# ha-pc-switch-revB.net
KiCad netlist of a schematic drawn in EAGLE
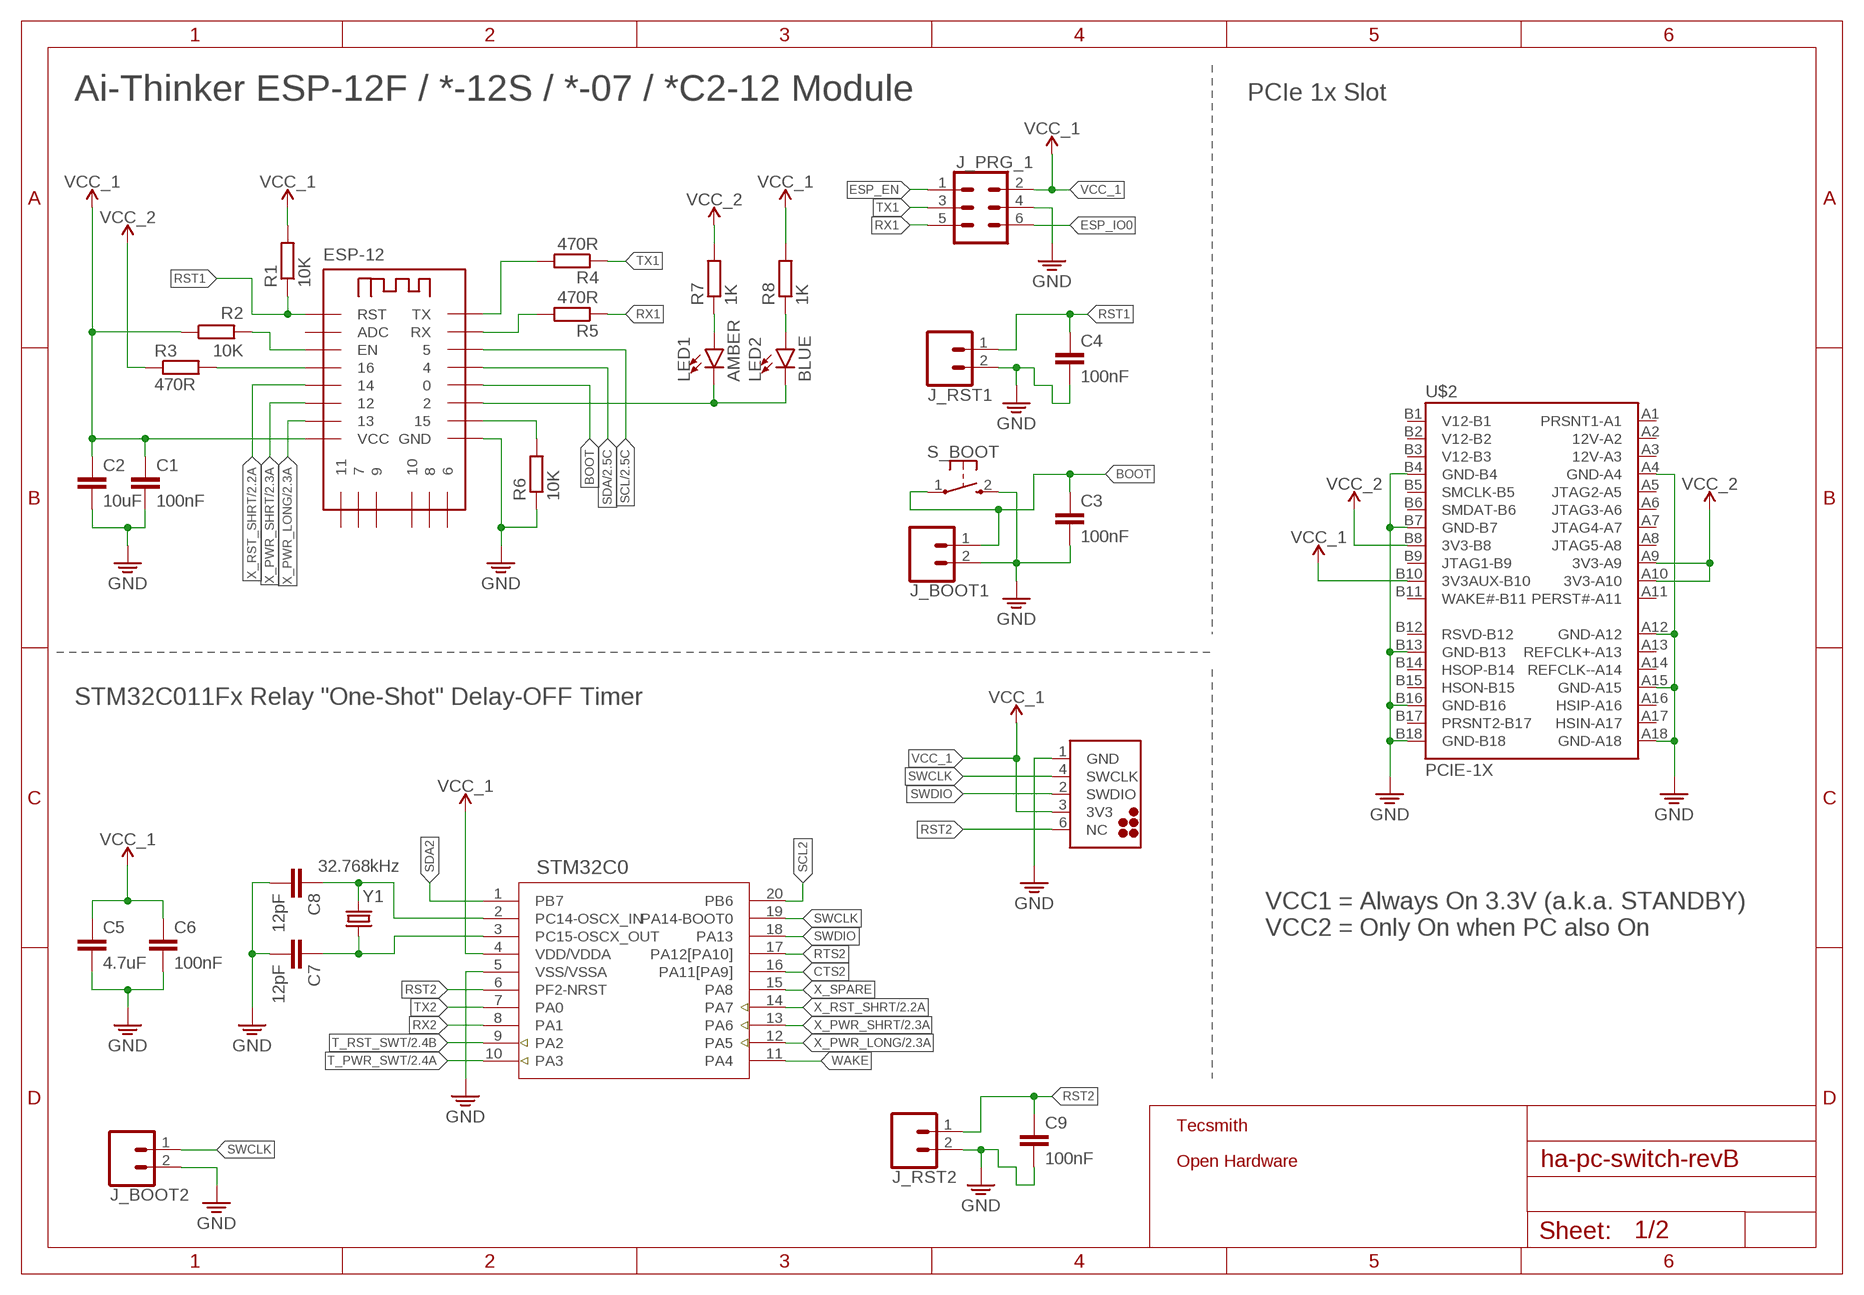
[diagram p0: schematic, sheet 1]
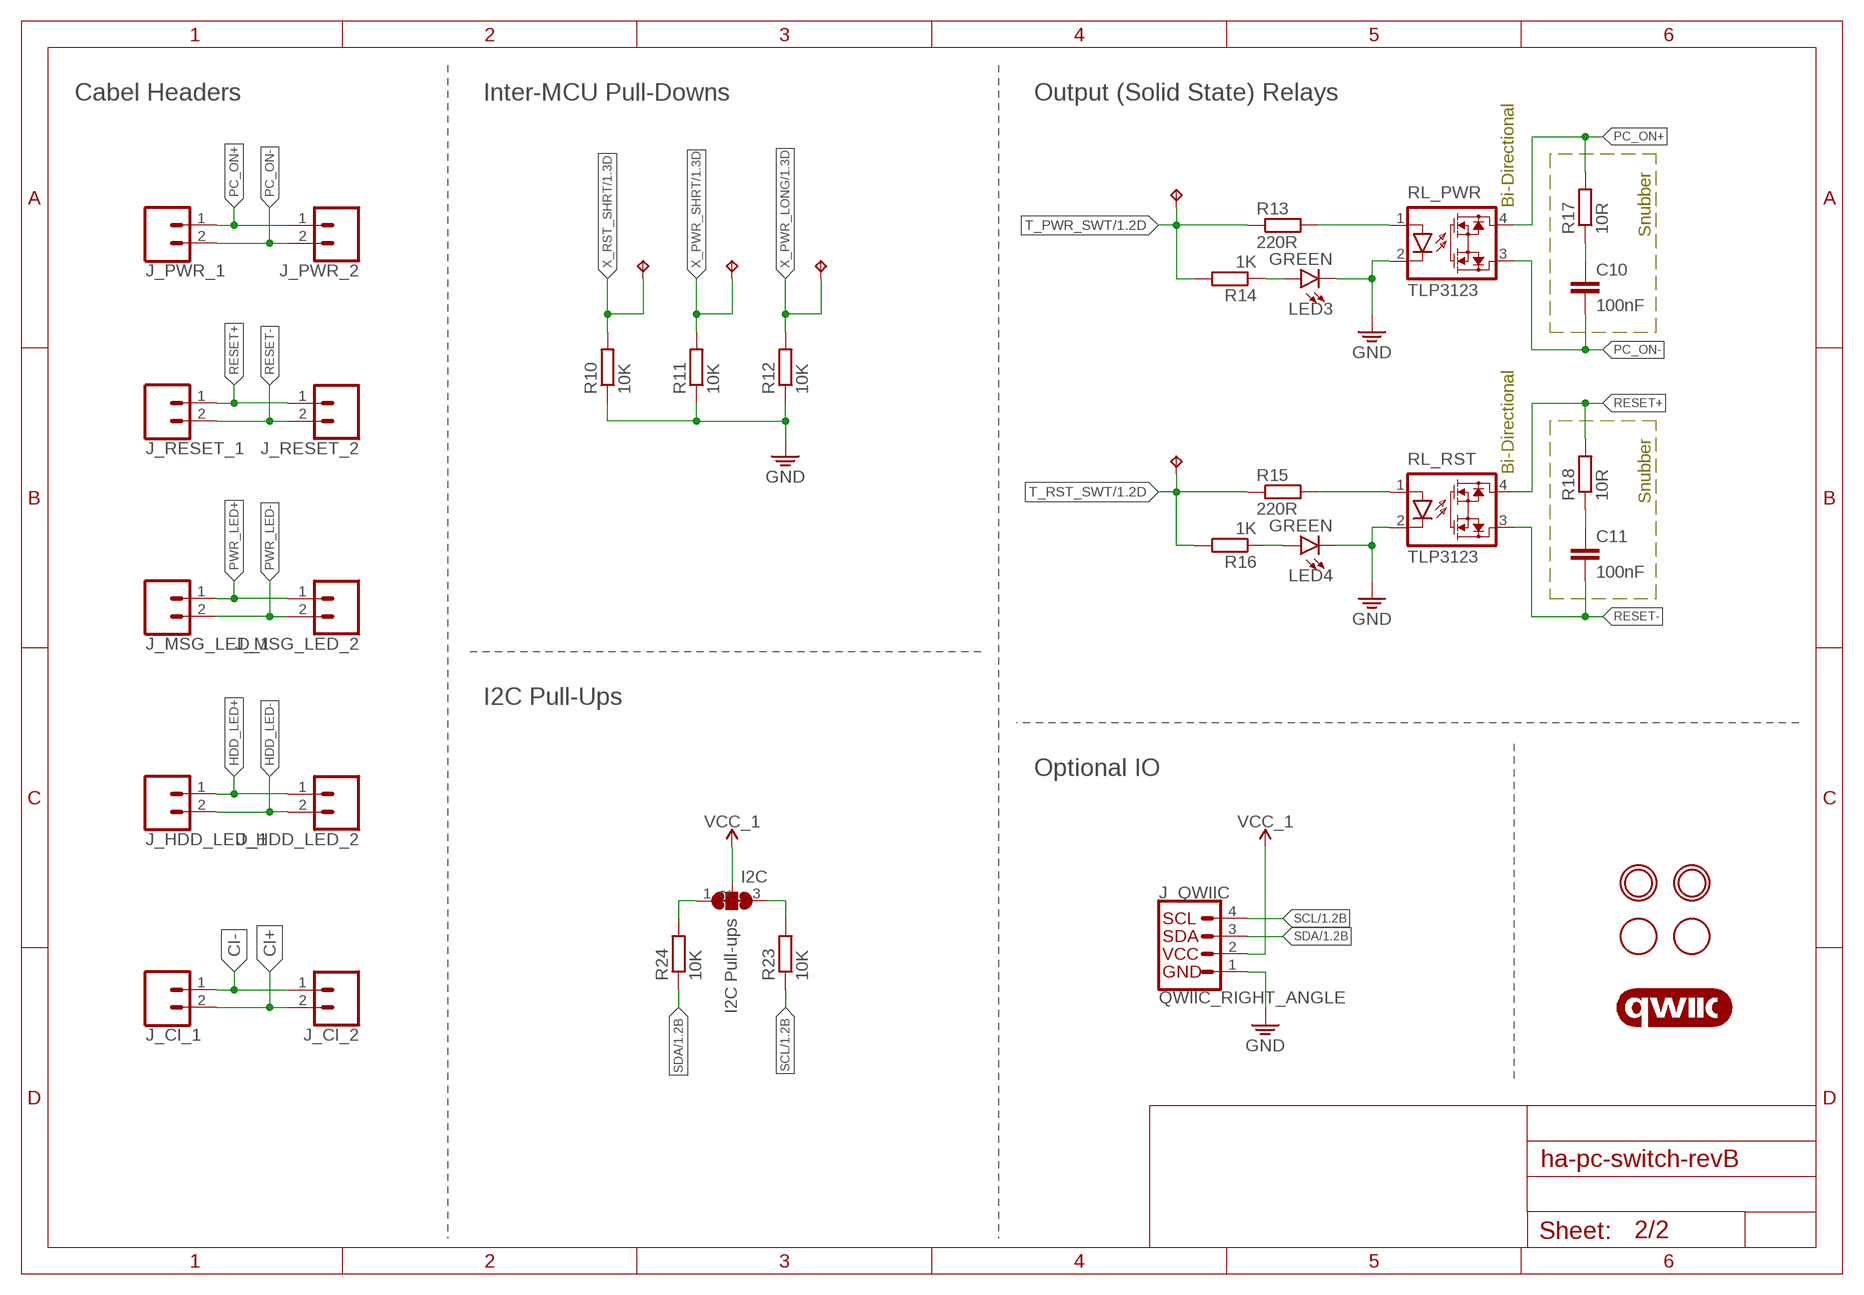
[diagram p1: schematic, sheet 2]

(export (version "E")
  (design (tool "Eeschema 10.0.6"))
  (components
    (comp (ref "C10")
      (value "100nF")
      (footprint "eagle-import:C0603")
      (libsource (lib "eagle-import") (part "C-EUC0603"))
    )
    (comp (ref "C11")
      (value "100nF")
      (footprint "eagle-import:C0603")
      (libsource (lib "eagle-import") (part "C-EUC0603"))
    )
    (comp (ref "I2C")
      (value "JUMPER-1X3-CLOSED-2")
      (footprint "eagle-import:SOLDERJUMPER_CLOSEDWIRE-3-2")
      (libsource (lib "eagle-import") (part "JUMPER-1X3-CLOSED-2"))
    )
    (comp (ref "J_CI_1")
      (value "CONN_021X02_NO_SILK")
      (footprint "eagle-import:1X02_NO_SILK")
      (libsource (lib "eagle-import") (part "CONN_021X02_NO_SILK"))
    )
    (comp (ref "J_CI_2")
      (value "CONN_021X02_NO_SILK")
      (footprint "eagle-import:1X02_NO_SILK")
      (libsource (lib "eagle-import") (part "CONN_021X02_NO_SILK"))
    )
    (comp (ref "J_HDD_LED_1")
      (value "CONN_021X02_NO_SILK")
      (footprint "eagle-import:1X02_NO_SILK")
      (libsource (lib "eagle-import") (part "CONN_021X02_NO_SILK"))
    )
    (comp (ref "J_HDD_LED_2")
      (value "CONN_021X02_NO_SILK")
      (footprint "eagle-import:1X02_NO_SILK")
      (libsource (lib "eagle-import") (part "CONN_021X02_NO_SILK"))
    )
    (comp (ref "J_MSG_LED_1")
      (value "CONN_021X02_NO_SILK")
      (footprint "eagle-import:1X02_NO_SILK")
      (libsource (lib "eagle-import") (part "CONN_021X02_NO_SILK"))
    )
    (comp (ref "J_MSG_LED_2")
      (value "CONN_021X02_NO_SILK")
      (footprint "eagle-import:1X02_NO_SILK")
      (libsource (lib "eagle-import") (part "CONN_021X02_NO_SILK"))
    )
    (comp (ref "J_PWR_1")
      (value "CONN_021X02_NO_SILK")
      (footprint "eagle-import:1X02_NO_SILK")
      (libsource (lib "eagle-import") (part "CONN_021X02_NO_SILK"))
    )
    (comp (ref "J_PWR_2")
      (value "CONN_021X02_NO_SILK")
      (footprint "eagle-import:1X02_NO_SILK")
      (libsource (lib "eagle-import") (part "CONN_021X02_NO_SILK"))
    )
    (comp (ref "J_QWIIC")
      (value "QWIIC_RIGHT_ANGLE")
      (footprint "eagle-import:JST04_1MM_RA")
      (libsource (lib "eagle-import") (part "QWIIC_CONNECTORJS-1MM"))
    )
    (comp (ref "J_RESET_1")
      (value "CONN_021X02_NO_SILK")
      (footprint "eagle-import:1X02_NO_SILK")
      (libsource (lib "eagle-import") (part "CONN_021X02_NO_SILK"))
    )
    (comp (ref "J_RESET_2")
      (value "CONN_021X02_NO_SILK")
      (footprint "eagle-import:1X02_NO_SILK")
      (libsource (lib "eagle-import") (part "CONN_021X02_NO_SILK"))
    )
    (comp (ref "LED3")
      (value "GREEN")
      (footprint "eagle-import:LED-0603")
      (libsource (lib "eagle-import") (part "LED-GREEN0603"))
    )
    (comp (ref "LED4")
      (value "GREEN")
      (footprint "eagle-import:LED-0603")
      (libsource (lib "eagle-import") (part "LED-GREEN0603"))
    )
    (comp (ref "LOGO2")
      (value "QWIIC_LOGO_4MM")
      (footprint "eagle-import:QWIIC_4MM")
      (libsource (lib "eagle-import") (part "QWIIC_LOGO_4MM"))
    )
    (comp (ref "R10")
      (value "10K")
      (footprint "eagle-import:R0603")
      (libsource (lib "eagle-import") (part "R-EU_R0603"))
    )
    (comp (ref "R11")
      (value "10K")
      (footprint "eagle-import:R0603")
      (libsource (lib "eagle-import") (part "R-EU_R0603"))
    )
    (comp (ref "R12")
      (value "10K")
      (footprint "eagle-import:R0603")
      (libsource (lib "eagle-import") (part "R-EU_R0603"))
    )
    (comp (ref "R13")
      (value "220R")
      (footprint "eagle-import:R0603")
      (libsource (lib "eagle-import") (part "R-EU_R0603"))
    )
    (comp (ref "R14")
      (value "1K")
      (footprint "eagle-import:R0603")
      (libsource (lib "eagle-import") (part "R-EU_R0603"))
    )
    (comp (ref "R15")
      (value "220R")
      (footprint "eagle-import:R0603")
      (libsource (lib "eagle-import") (part "R-EU_R0603"))
    )
    (comp (ref "R16")
      (value "1K")
      (footprint "eagle-import:R0603")
      (libsource (lib "eagle-import") (part "R-EU_R0603"))
    )
    (comp (ref "R17")
      (value "10R")
      (footprint "eagle-import:R0603")
      (libsource (lib "eagle-import") (part "R-EU_R0603"))
    )
    (comp (ref "R18")
      (value "10R")
      (footprint "eagle-import:R0603")
      (libsource (lib "eagle-import") (part "R-EU_R0603"))
    )
    (comp (ref "R23")
      (value "10K")
      (footprint "eagle-import:R0603")
      (libsource (lib "eagle-import") (part "R-EU_R0603"))
    )
    (comp (ref "R24")
      (value "10K")
      (footprint "eagle-import:R0603")
      (libsource (lib "eagle-import") (part "R-EU_R0603"))
    )
    (comp (ref "RL_PWR")
      (value "TLP3123")
      (footprint "eagle-import:SOP4_TOS")
      (libsource (lib "eagle-import") (part "TLP3123"))
    )
    (comp (ref "RL_RST")
      (value "TLP3123")
      (footprint "eagle-import:SOP4_TOS")
      (libsource (lib "eagle-import") (part "TLP3123"))
    )
    (comp (ref "TP6")
      (value "TPTP16SQ")
      (footprint "eagle-import:TP16SQ")
      (libsource (lib "eagle-import") (part "TPTP16SQ"))
    )
    (comp (ref "TP7")
      (value "TPTP16SQ")
      (footprint "eagle-import:TP16SQ")
      (libsource (lib "eagle-import") (part "TPTP16SQ"))
    )
    (comp (ref "TP8")
      (value "TPTP16SQ")
      (footprint "eagle-import:TP16SQ")
      (libsource (lib "eagle-import") (part "TPTP16SQ"))
    )
    (comp (ref "TP9")
      (value "TPTP16SQ")
      (footprint "eagle-import:TP16SQ")
      (libsource (lib "eagle-import") (part "TPTP16SQ"))
    )
    (comp (ref "TP10")
      (value "TPTP16SQ")
      (footprint "eagle-import:TP16SQ")
      (libsource (lib "eagle-import") (part "TPTP16SQ"))
    )
    (comp (ref "U$9")
      (value "MOUNTINGHOLE3.0THIN")
      (footprint "eagle-import:MOUNTINGHOLE_3.0_PLATEDTHIN")
      (libsource (lib "eagle-import") (part "MOUNTINGHOLE3.0THIN"))
    )
    (comp (ref "U$11")
      (value "MOUNTINGHOLE3.0THIN")
      (footprint "eagle-import:MOUNTINGHOLE_3.0_PLATEDTHIN")
      (libsource (lib "eagle-import") (part "MOUNTINGHOLE3.0THIN"))
    )
    (comp (ref "U$15")
      (value "FIDUCIAL")
      (footprint "eagle-import:FIDUCIAL_1MM")
      (libsource (lib "eagle-import") (part "FIDUCIAL"))
    )
    (comp (ref "U$16")
      (value "FIDUCIAL")
      (footprint "eagle-import:FIDUCIAL_1MM")
      (libsource (lib "eagle-import") (part "FIDUCIAL"))
    )
    (comp (ref "C1")
      (value "100nF")
      (footprint "eagle-import:C0603")
      (libsource (lib "eagle-import") (part "C-EUC0603"))
    )
    (comp (ref "C2")
      (value "10uF")
      (footprint "eagle-import:C0603")
      (libsource (lib "eagle-import") (part "C-EUC0603"))
    )
    (comp (ref "C3")
      (value "100nF")
      (footprint "eagle-import:C0603")
      (libsource (lib "eagle-import") (part "C-EUC0603"))
    )
    (comp (ref "C4")
      (value "100nF")
      (footprint "eagle-import:C0603")
      (libsource (lib "eagle-import") (part "C-EUC0603"))
    )
    (comp (ref "C5")
      (value "4.7uF")
      (footprint "eagle-import:C0603")
      (libsource (lib "eagle-import") (part "C-EUC0603"))
    )
    (comp (ref "C6")
      (value "100nF")
      (footprint "eagle-import:C0603")
      (libsource (lib "eagle-import") (part "C-EUC0603"))
    )
    (comp (ref "C7")
      (value "12pF")
      (footprint "eagle-import:C0603")
      (libsource (lib "eagle-import") (part "C-EUC0603"))
    )
    (comp (ref "C8")
      (value "12pF")
      (footprint "eagle-import:C0603")
      (libsource (lib "eagle-import") (part "C-EUC0603"))
    )
    (comp (ref "C9")
      (value "100nF")
      (footprint "eagle-import:C0603")
      (libsource (lib "eagle-import") (part "C-EUC0603"))
    )
    (comp (ref "ESP-12")
      (value "ESPRESSIF-ESP-12F&ESMD")
      (footprint "eagle-import:ESP8266-ESP-12E")
      (libsource (lib "eagle-import") (part "ESPRESSIF-ESP-12F&ESMD"))
    )
    (comp (ref "J_BOOT1")
      (value "CONN_021X02_NO_SILK")
      (footprint "eagle-import:1X02_NO_SILK")
      (libsource (lib "eagle-import") (part "CONN_021X02_NO_SILK"))
    )
    (comp (ref "J_BOOT2")
      (value "CONN_021X02_NO_SILK")
      (footprint "eagle-import:1X02_NO_SILK")
      (libsource (lib "eagle-import") (part "CONN_021X02_NO_SILK"))
    )
    (comp (ref "J_PRG2")
      (value "NUCLEO_HEADER")
      (footprint "eagle-import:NUCLEO")
      (libsource (lib "eagle-import") (part "NUCLEO_HEADER"))
    )
    (comp (ref "J_PRG_1")
      (value "CONN_03X2NO_SILK")
      (footprint "eagle-import:2X3-NS")
      (libsource (lib "eagle-import") (part "CONN_03X2NO_SILK"))
    )
    (comp (ref "J_RST1")
      (value "CONN_021X02_NO_SILK")
      (footprint "eagle-import:1X02_NO_SILK")
      (libsource (lib "eagle-import") (part "CONN_021X02_NO_SILK"))
    )
    (comp (ref "J_RST2")
      (value "CONN_021X02_NO_SILK")
      (footprint "eagle-import:1X02_NO_SILK")
      (libsource (lib "eagle-import") (part "CONN_021X02_NO_SILK"))
    )
    (comp (ref "LED1")
      (value "AMBER")
      (footprint "eagle-import:LED-0603")
      (libsource (lib "eagle-import") (part "LED-GREEN0603"))
    )
    (comp (ref "LED2")
      (value "BLUE")
      (footprint "eagle-import:LED-0603")
      (libsource (lib "eagle-import") (part "LED-GREEN0603"))
    )
    (comp (ref "LOGO1")
      (value "OSHW-LOGOM")
      (footprint "eagle-import:OSHW-LOGO-M")
      (libsource (lib "eagle-import") (part "OSHW-LOGOM"))
    )
    (comp (ref "R1")
      (value "10K")
      (footprint "eagle-import:R0603")
      (libsource (lib "eagle-import") (part "R-EU_R0603"))
    )
    (comp (ref "R2")
      (value "10K")
      (footprint "eagle-import:R0603")
      (libsource (lib "eagle-import") (part "R-EU_R0603"))
    )
    (comp (ref "R3")
      (value "470R")
      (footprint "eagle-import:R0603")
      (libsource (lib "eagle-import") (part "R-EU_R0603"))
    )
    (comp (ref "R4")
      (value "470R")
      (footprint "eagle-import:R0603")
      (libsource (lib "eagle-import") (part "R-EU_R0603"))
    )
    (comp (ref "R5")
      (value "470R")
      (footprint "eagle-import:R0603")
      (libsource (lib "eagle-import") (part "R-EU_R0603"))
    )
    (comp (ref "R6")
      (value "10K")
      (footprint "eagle-import:R0603")
      (libsource (lib "eagle-import") (part "R-EU_R0603"))
    )
    (comp (ref "R7")
      (value "1K")
      (footprint "eagle-import:R0603")
      (libsource (lib "eagle-import") (part "R-EU_R0603"))
    )
    (comp (ref "R8")
      (value "1K")
      (footprint "eagle-import:R0603")
      (libsource (lib "eagle-import") (part "R-EU_R0603"))
    )
    (comp (ref "STM32C0")
      (value "STM32C011FTSSOP20_STM-M")
      (footprint "eagle-import:TSSOP20-M")
      (fields
        (field (name "MANUFACTURER_PART_NUMBER") "STM32C011F4P6")
        (field (name "COPYRIGHT") "Copyright (C) 2024 Ultra Librarian. All rights reserved.")
      )
      (libsource (lib "eagle-import") (part "STM32C011FTSSOP20_STM-M"))
    )
    (comp (ref "S_BOOT")
      (value "MOMENTARY-SWITCH-SPST-1")
      (footprint "eagle-import:SKRKAEE020")
      (libsource (lib "eagle-import") (part "MOMENTARY-SWITCH-SPST-1"))
    )
    (comp (ref "U$1")
      (value "TECSMITH-LOGOLONG")
      (footprint "eagle-import:TECSMITH-NAME")
      (libsource (lib "eagle-import") (part "TECSMITH-LOGOLONG"))
    )
    (comp (ref "U$2")
      (value "PCIE-1X")
      (footprint "eagle-import:PCIE-1X")
      (libsource (lib "eagle-import") (part "PCIE-1X"))
    )
    (comp (ref "Y1")
      (value "32.768kHz")
      (footprint "eagle-import:CRYSTAL-SMD-3.2X1.5MM")
      (libsource (lib "eagle-import") (part "CRYSTAL-32.768KHZSMD-3.2X1.5"))
    )
  )
  (nets
    (net (code "1") (name "BOOT") (class "Default")
      (node (ref "C3") (pin "1") (pinfunction "1_1") (pintype "passive"))
      (node (ref "ESP-12") (pin "GPIO0") (pinfunction "0_GPIO0") (pintype "bidirectional"))
      (node (ref "J_BOOT1") (pin "1") (pinfunction "1_1") (pintype "passive"))
      (node (ref "S_BOOT") (pin "1") (pinfunction "1_1") (pintype "passive"))
    )
    (net (code "2") (name "CI+") (class "Default")
      (node (ref "J_CI_1") (pin "2") (pinfunction "2_2") (pintype "passive"))
      (node (ref "J_CI_2") (pin "2") (pinfunction "2_2") (pintype "passive"))
    )
    (net (code "3") (name "CI-") (class "Default")
      (node (ref "J_CI_1") (pin "1") (pinfunction "1_1") (pintype "passive"))
      (node (ref "J_CI_2") (pin "1") (pinfunction "1_1") (pintype "passive"))
    )
    (net (code "4") (name "CTS2") (class "Default")
      (node (ref "STM32C0") (pin "16") (pinfunction "PA11[PA9]_16") (pintype "bidirectional"))
    )
    (net (code "5") (name "ESP_EN") (class "Default")
      (node (ref "ESP-12") (pin "EN") (pinfunction "EN_EN") (pintype "bidirectional"))
      (node (ref "J_PRG_1") (pin "1") (pinfunction "1_1") (pintype "bidirectional"))
      (node (ref "R2") (pin "2") (pinfunction "2_2") (pintype "passive"))
    )
    (net (code "6") (name "ESP_IO0") (class "Default")
      (node (ref "J_PRG_1") (pin "6") (pinfunction "6_6") (pintype "bidirectional"))
    )
    (net (code "7") (name "GND") (class "Default")
      (node (ref "C1") (pin "2") (pinfunction "2_2") (pintype "passive"))
      (node (ref "C2") (pin "2") (pinfunction "2_2") (pintype "passive"))
      (node (ref "C3") (pin "2") (pinfunction "2_2") (pintype "passive"))
      (node (ref "C4") (pin "2") (pinfunction "2_2") (pintype "passive"))
      (node (ref "C5") (pin "2") (pinfunction "2_2") (pintype "passive"))
      (node (ref "C6") (pin "2") (pinfunction "2_2") (pintype "passive"))
      (node (ref "C7") (pin "2") (pinfunction "2_2") (pintype "passive"))
      (node (ref "C8") (pin "2") (pinfunction "2_2") (pintype "passive"))
      (node (ref "C9") (pin "2") (pinfunction "2_2") (pintype "passive"))
      (node (ref "ESP-12") (pin "GND") (pinfunction "GND_GND") (pintype "bidirectional"))
      (node (ref "J_BOOT1") (pin "2") (pinfunction "2_2") (pintype "passive"))
      (node (ref "J_BOOT2") (pin "2") (pinfunction "2_2") (pintype "passive"))
      (node (ref "J_PRG2") (pin "1") (pinfunction "GND_1") (pintype "power_in"))
      (node (ref "J_PRG_1") (pin "4") (pinfunction "4_4") (pintype "bidirectional"))
      (node (ref "J_QWIIC") (pin "1") (pinfunction "1_1") (pintype "power_in"))
      (node (ref "J_RST1") (pin "2") (pinfunction "2_2") (pintype "passive"))
      (node (ref "J_RST2") (pin "2") (pinfunction "2_2") (pintype "passive"))
      (node (ref "LED3") (pin "C") (pinfunction "C_C") (pintype "passive"))
      (node (ref "LED4") (pin "C") (pinfunction "C_C") (pintype "passive"))
      (node (ref "R10") (pin "1") (pinfunction "1_1") (pintype "passive"))
      (node (ref "R11") (pin "1") (pinfunction "1_1") (pintype "passive"))
      (node (ref "R12") (pin "1") (pinfunction "1_1") (pintype "passive"))
      (node (ref "R6") (pin "1") (pinfunction "1_1") (pintype "passive"))
      (node (ref "RL_PWR") (pin "2") (pinfunction "C_2") (pintype "passive"))
      (node (ref "RL_RST") (pin "2") (pinfunction "C_2") (pintype "passive"))
      (node (ref "STM32C0") (pin "5") (pinfunction "VSS/VSSA_5") (pintype "power_in"))
      (node (ref "S_BOOT") (pin "2") (pinfunction "3_2") (pintype "passive"))
      (node (ref "U$2") (pin "A12") (pinfunction "GND-A12_A12") (pintype "bidirectional"))
      (node (ref "U$2") (pin "A15") (pinfunction "GND-A15_A15") (pintype "bidirectional"))
      (node (ref "U$2") (pin "A18") (pinfunction "GND-A18_A18") (pintype "bidirectional"))
      (node (ref "U$2") (pin "A4") (pinfunction "GND-A4_A4") (pintype "bidirectional"))
      (node (ref "U$2") (pin "B13") (pinfunction "GND-B13_B13") (pintype "bidirectional"))
      (node (ref "U$2") (pin "B16") (pinfunction "GND-B16_B16") (pintype "bidirectional"))
      (node (ref "U$2") (pin "B18") (pinfunction "GND-B18_B18") (pintype "bidirectional"))
      (node (ref "U$2") (pin "B4") (pinfunction "GND-B4_B4") (pintype "bidirectional"))
      (node (ref "U$2") (pin "B7") (pinfunction "GND-B7_B7") (pintype "bidirectional"))
    )
    (net (code "8") (name "HDD_LED+") (class "Default")
      (node (ref "J_HDD_LED_1") (pin "1") (pinfunction "1_1") (pintype "passive"))
      (node (ref "J_HDD_LED_2") (pin "1") (pinfunction "1_1") (pintype "passive"))
    )
    (net (code "9") (name "HDD_LED-") (class "Default")
      (node (ref "J_HDD_LED_1") (pin "2") (pinfunction "2_2") (pintype "passive"))
      (node (ref "J_HDD_LED_2") (pin "2") (pinfunction "2_2") (pintype "passive"))
    )
    (net (code "10") (name "Net-(C10-Pad1)") (class "Default")
      (node (ref "C10") (pin "1") (pinfunction "1_1") (pintype "passive"))
      (node (ref "R17") (pin "1") (pinfunction "1_1") (pintype "passive"))
    )
    (net (code "11") (name "Net-(C11-Pad1)") (class "Default")
      (node (ref "C11") (pin "1") (pinfunction "1_1") (pintype "passive"))
      (node (ref "R18") (pin "1") (pinfunction "1_1") (pintype "passive"))
    )
    (net (code "12") (name "Net-(ESP-12-2)") (class "Default")
      (node (ref "ESP-12") (pin "GPIO2") (pinfunction "2_GPIO2") (pintype "bidirectional"))
      (node (ref "LED1") (pin "C") (pinfunction "C_C") (pintype "passive"))
      (node (ref "LED2") (pin "C") (pinfunction "C_C") (pintype "passive"))
    )
    (net (code "13") (name "Net-(ESP-12-15)") (class "Default")
      (node (ref "ESP-12") (pin "GPIO15") (pinfunction "15_GPIO15") (pintype "bidirectional"))
      (node (ref "R6") (pin "2") (pinfunction "2_2") (pintype "passive"))
    )
    (net (code "14") (name "Net-(ESP-12-16)") (class "Default")
      (node (ref "ESP-12") (pin "GPIO16") (pinfunction "16_GPIO16") (pintype "bidirectional"))
      (node (ref "R3") (pin "2") (pinfunction "2_2") (pintype "passive"))
    )
    (net (code "15") (name "Net-(ESP-12-RX)") (class "Default")
      (node (ref "ESP-12") (pin "RXD0") (pinfunction "RX_RXD0") (pintype "bidirectional"))
      (node (ref "R5") (pin "2") (pinfunction "2_2") (pintype "passive"))
    )
    (net (code "16") (name "Net-(ESP-12-TX)") (class "Default")
      (node (ref "ESP-12") (pin "TXD0") (pinfunction "TX_TXD0") (pintype "bidirectional"))
      (node (ref "R4") (pin "2") (pinfunction "2_2") (pintype "passive"))
    )
    (net (code "17") (name "Net-(I2C-Pad1)") (class "Default")
      (node (ref "I2C") (pin "1") (pinfunction "1_1") (pintype "passive"))
      (node (ref "R24") (pin "2") (pinfunction "2_2") (pintype "passive"))
    )
    (net (code "18") (name "Net-(I2C-Pad3)") (class "Default")
      (node (ref "I2C") (pin "3") (pinfunction "3_3") (pintype "passive"))
      (node (ref "R23") (pin "2") (pinfunction "2_2") (pintype "passive"))
    )
    (net (code "19") (name "Net-(LED1-PadA)") (class "Default")
      (node (ref "LED1") (pin "A") (pinfunction "A_A") (pintype "passive"))
      (node (ref "R7") (pin "1") (pinfunction "1_1") (pintype "passive"))
    )
    (net (code "20") (name "Net-(LED2-PadA)") (class "Default")
      (node (ref "LED2") (pin "A") (pinfunction "A_A") (pintype "passive"))
      (node (ref "R8") (pin "1") (pinfunction "1_1") (pintype "passive"))
    )
    (net (code "21") (name "Net-(LED3-PadA)") (class "Default")
      (node (ref "LED3") (pin "A") (pinfunction "A_A") (pintype "passive"))
      (node (ref "R14") (pin "1") (pinfunction "1_1") (pintype "passive"))
    )
    (net (code "22") (name "Net-(LED4-PadA)") (class "Default")
      (node (ref "LED4") (pin "A") (pinfunction "A_A") (pintype "passive"))
      (node (ref "R16") (pin "1") (pinfunction "1_1") (pintype "passive"))
    )
    (net (code "23") (name "Net-(RL_PWR-A)") (class "Default")
      (node (ref "R13") (pin "2") (pinfunction "2_2") (pintype "passive"))
      (node (ref "RL_PWR") (pin "1") (pinfunction "A_1") (pintype "passive"))
    )
    (net (code "24") (name "Net-(RL_RST-A)") (class "Default")
      (node (ref "R15") (pin "2") (pinfunction "2_2") (pintype "passive"))
      (node (ref "RL_RST") (pin "1") (pinfunction "A_1") (pintype "passive"))
    )
    (net (code "25") (name "Net-(STM32C0-PC14-OSCX_IN)") (class "Default")
      (node (ref "C8") (pin "1") (pinfunction "1_1") (pintype "passive"))
      (node (ref "STM32C0") (pin "2") (pinfunction "PC14-OSCX_IN_2") (pintype "bidirectional"))
      (node (ref "Y1") (pin "P$2") (pinfunction "2_P$2") (pintype "passive"))
    )
    (net (code "26") (name "Net-(STM32C0-PC15-OSCX_OUT)") (class "Default")
      (node (ref "C7") (pin "1") (pinfunction "1_1") (pintype "passive"))
      (node (ref "STM32C0") (pin "3") (pinfunction "PC15-OSCX_OUT_3") (pintype "bidirectional"))
      (node (ref "Y1") (pin "P$1") (pinfunction "1_P$1") (pintype "passive"))
    )
    (net (code "27") (name "PC_ON+") (class "Default")
      (node (ref "J_PWR_1") (pin "1") (pinfunction "1_1") (pintype "passive"))
      (node (ref "J_PWR_2") (pin "1") (pinfunction "1_1") (pintype "passive"))
      (node (ref "R17") (pin "2") (pinfunction "2_2") (pintype "passive"))
      (node (ref "RL_PWR") (pin "4") (pinfunction "D1_4") (pintype "passive"))
    )
    (net (code "28") (name "PC_ON-") (class "Default")
      (node (ref "C10") (pin "2") (pinfunction "2_2") (pintype "passive"))
      (node (ref "J_PWR_1") (pin "2") (pinfunction "2_2") (pintype "passive"))
      (node (ref "J_PWR_2") (pin "2") (pinfunction "2_2") (pintype "passive"))
      (node (ref "RL_PWR") (pin "3") (pinfunction "D2_3") (pintype "passive"))
    )
    (net (code "29") (name "PWR_LED+") (class "Default")
      (node (ref "J_MSG_LED_1") (pin "1") (pinfunction "1_1") (pintype "passive"))
      (node (ref "J_MSG_LED_2") (pin "1") (pinfunction "1_1") (pintype "passive"))
    )
    (net (code "30") (name "PWR_LED-") (class "Default")
      (node (ref "J_MSG_LED_1") (pin "2") (pinfunction "2_2") (pintype "passive"))
      (node (ref "J_MSG_LED_2") (pin "2") (pinfunction "2_2") (pintype "passive"))
    )
    (net (code "31") (name "RESET+") (class "Default")
      (node (ref "J_RESET_1") (pin "1") (pinfunction "1_1") (pintype "passive"))
      (node (ref "J_RESET_2") (pin "1") (pinfunction "1_1") (pintype "passive"))
      (node (ref "R18") (pin "2") (pinfunction "2_2") (pintype "passive"))
      (node (ref "RL_RST") (pin "4") (pinfunction "D1_4") (pintype "passive"))
    )
    (net (code "32") (name "RESET-") (class "Default")
      (node (ref "C11") (pin "2") (pinfunction "2_2") (pintype "passive"))
      (node (ref "J_RESET_1") (pin "2") (pinfunction "2_2") (pintype "passive"))
      (node (ref "J_RESET_2") (pin "2") (pinfunction "2_2") (pintype "passive"))
      (node (ref "RL_RST") (pin "3") (pinfunction "D2_3") (pintype "passive"))
    )
    (net (code "33") (name "RST1") (class "Default")
      (node (ref "C4") (pin "1") (pinfunction "1_1") (pintype "passive"))
      (node (ref "ESP-12") (pin "RST") (pinfunction "RST_RST") (pintype "bidirectional"))
      (node (ref "J_RST1") (pin "1") (pinfunction "1_1") (pintype "passive"))
      (node (ref "R1") (pin "1") (pinfunction "1_1") (pintype "passive"))
    )
    (net (code "34") (name "RST2") (class "Default")
      (node (ref "C9") (pin "1") (pinfunction "1_1") (pintype "passive"))
      (node (ref "J_PRG2") (pin "6") (pinfunction "NC_6") (pintype "passive"))
      (node (ref "J_RST2") (pin "1") (pinfunction "1_1") (pintype "passive"))
      (node (ref "STM32C0") (pin "6") (pinfunction "PF2-NRST_6") (pintype "bidirectional"))
    )
    (net (code "35") (name "RTS2") (class "Default")
      (node (ref "STM32C0") (pin "17") (pinfunction "PA12[PA10]_17") (pintype "bidirectional"))
    )
    (net (code "36") (name "RX1") (class "Default")
      (node (ref "J_PRG_1") (pin "5") (pinfunction "5_5") (pintype "bidirectional"))
      (node (ref "R5") (pin "1") (pinfunction "1_1") (pintype "passive"))
    )
    (net (code "37") (name "RX2") (class "Default")
      (node (ref "STM32C0") (pin "8") (pinfunction "PA1_8") (pintype "bidirectional"))
    )
    (net (code "38") (name "SCL") (class "Default")
      (node (ref "ESP-12") (pin "GPIO5") (pinfunction "5_GPIO5") (pintype "bidirectional"))
      (node (ref "J_QWIIC") (pin "4") (pinfunction "4_4") (pintype "passive"))
      (node (ref "R23") (pin "1") (pinfunction "1_1") (pintype "passive"))
    )
    (net (code "39") (name "SCL2") (class "Default")
      (node (ref "STM32C0") (pin "20") (pinfunction "PB6_20") (pintype "bidirectional"))
    )
    (net (code "40") (name "SDA") (class "Default")
      (node (ref "ESP-12") (pin "GPIO4") (pinfunction "4_GPIO4") (pintype "bidirectional"))
      (node (ref "J_QWIIC") (pin "3") (pinfunction "3_3") (pintype "passive"))
      (node (ref "R24") (pin "1") (pinfunction "1_1") (pintype "passive"))
    )
    (net (code "41") (name "SDA2") (class "Default")
      (node (ref "STM32C0") (pin "1") (pinfunction "PB7_1") (pintype "bidirectional"))
    )
    (net (code "42") (name "SWCLK") (class "Default")
      (node (ref "J_BOOT2") (pin "1") (pinfunction "1_1") (pintype "passive"))
      (node (ref "J_PRG2") (pin "4") (pinfunction "SWCLK_4") (pintype "output"))
      (node (ref "STM32C0") (pin "19") (pinfunction "PA14-BOOT0_19") (pintype "bidirectional"))
    )
    (net (code "43") (name "SWDIO") (class "Default")
      (node (ref "J_PRG2") (pin "2") (pinfunction "SWDIO_2") (pintype "bidirectional"))
      (node (ref "STM32C0") (pin "18") (pinfunction "PA13_18") (pintype "bidirectional"))
    )
    (net (code "44") (name "TX1") (class "Default")
      (node (ref "J_PRG_1") (pin "3") (pinfunction "3_3") (pintype "bidirectional"))
      (node (ref "R4") (pin "1") (pinfunction "1_1") (pintype "passive"))
    )
    (net (code "45") (name "TX2") (class "Default")
      (node (ref "STM32C0") (pin "7") (pinfunction "PA0_7") (pintype "bidirectional"))
    )
    (net (code "46") (name "T_PWR_SWT") (class "Default")
      (node (ref "R13") (pin "1") (pinfunction "1_1") (pintype "passive"))
      (node (ref "R14") (pin "2") (pinfunction "2_2") (pintype "passive"))
      (node (ref "STM32C0") (pin "10") (pinfunction "PA3_10") (pintype "bidirectional"))
      (node (ref "TP9") (pin "TP") (pinfunction "TP_TP") (pintype "input"))
    )
    (net (code "47") (name "T_RST_SWT") (class "Default")
      (node (ref "R15") (pin "1") (pinfunction "1_1") (pintype "passive"))
      (node (ref "R16") (pin "2") (pinfunction "2_2") (pintype "passive"))
      (node (ref "STM32C0") (pin "9") (pinfunction "PA2_9") (pintype "bidirectional"))
      (node (ref "TP10") (pin "TP") (pinfunction "TP_TP") (pintype "input"))
    )
    (net (code "48") (name "VCC_1") (class "Default")
      (node (ref "C1") (pin "1") (pinfunction "1_1") (pintype "passive"))
      (node (ref "C2") (pin "1") (pinfunction "1_1") (pintype "passive"))
      (node (ref "C5") (pin "1") (pinfunction "1_1") (pintype "passive"))
      (node (ref "C6") (pin "1") (pinfunction "1_1") (pintype "passive"))
      (node (ref "ESP-12") (pin "VCC") (pinfunction "VCC_VCC") (pintype "bidirectional"))
      (node (ref "I2C") (pin "2") (pinfunction "2_2") (pintype "passive"))
      (node (ref "J_PRG2") (pin "3") (pinfunction "3V3_3") (pintype "power_in"))
      (node (ref "J_PRG_1") (pin "2") (pinfunction "2_2") (pintype "bidirectional"))
      (node (ref "J_QWIIC") (pin "2") (pinfunction "2_2") (pintype "power_in"))
      (node (ref "R1") (pin "2") (pinfunction "2_2") (pintype "passive"))
      (node (ref "R2") (pin "1") (pinfunction "1_1") (pintype "passive"))
      (node (ref "R8") (pin "2") (pinfunction "2_2") (pintype "passive"))
      (node (ref "STM32C0") (pin "4") (pinfunction "VDD/VDDA_4") (pintype "power_in"))
      (node (ref "U$2") (pin "B10") (pinfunction "3V3AUX-B10_B10") (pintype "bidirectional"))
    )
    (net (code "49") (name "VCC_2") (class "Default")
      (node (ref "R3") (pin "1") (pinfunction "1_1") (pintype "passive"))
      (node (ref "R7") (pin "2") (pinfunction "2_2") (pintype "passive"))
      (node (ref "U$2") (pin "A10") (pinfunction "3V3-A10_A10") (pintype "bidirectional"))
      (node (ref "U$2") (pin "A9") (pinfunction "3V3-A9_A9") (pintype "bidirectional"))
      (node (ref "U$2") (pin "B8") (pinfunction "3V3-B8_B8") (pintype "bidirectional"))
    )
    (net (code "50") (name "WAKE") (class "Default")
      (node (ref "STM32C0") (pin "11") (pinfunction "PA4_11") (pintype "bidirectional"))
    )
    (net (code "51") (name "X_PWR_LONG") (class "Default")
      (node (ref "ESP-12") (pin "GPIO13") (pinfunction "13_GPIO13") (pintype "bidirectional"))
      (node (ref "R12") (pin "2") (pinfunction "2_2") (pintype "passive"))
      (node (ref "STM32C0") (pin "12") (pinfunction "PA5_12") (pintype "bidirectional"))
      (node (ref "TP8") (pin "TP") (pinfunction "TP_TP") (pintype "input"))
    )
    (net (code "52") (name "X_PWR_SHRT") (class "Default")
      (node (ref "ESP-12") (pin "GPIO12") (pinfunction "12_GPIO12") (pintype "bidirectional"))
      (node (ref "R11") (pin "2") (pinfunction "2_2") (pintype "passive"))
      (node (ref "STM32C0") (pin "13") (pinfunction "PA6_13") (pintype "bidirectional"))
      (node (ref "TP7") (pin "TP") (pinfunction "TP_TP") (pintype "input"))
    )
    (net (code "53") (name "X_RST_SHRT") (class "Default")
      (node (ref "ESP-12") (pin "GPIO14") (pinfunction "14_GPIO14") (pintype "bidirectional"))
      (node (ref "R10") (pin "2") (pinfunction "2_2") (pintype "passive"))
      (node (ref "STM32C0") (pin "14") (pinfunction "PA7_14") (pintype "bidirectional"))
      (node (ref "TP6") (pin "TP") (pinfunction "TP_TP") (pintype "input"))
    )
    (net (code "54") (name "X_SPARE") (class "Default")
      (node (ref "STM32C0") (pin "15") (pinfunction "PA8_15") (pintype "bidirectional"))
    )
    (net (code "55") (name "unconnected-(ESP-12-6-PadSCLK)") (class "Default")
      (node (ref "ESP-12") (pin "SCLK") (pinfunction "6_SCLK") (pintype "bidirectional"))
    )
    (net (code "56") (name "unconnected-(ESP-12-7-PadMISO)") (class "Default")
      (node (ref "ESP-12") (pin "MISO") (pinfunction "7_MISO") (pintype "bidirectional"))
    )
    (net (code "57") (name "unconnected-(ESP-12-8-PadMOSI)") (class "Default")
      (node (ref "ESP-12") (pin "MOSI") (pinfunction "8_MOSI") (pintype "bidirectional"))
    )
    (net (code "58") (name "unconnected-(ESP-12-9-PadGPIO9)") (class "Default")
      (node (ref "ESP-12") (pin "GPIO9") (pinfunction "9_GPIO9") (pintype "bidirectional"))
    )
    (net (code "59") (name "unconnected-(ESP-12-10-PadGPIO10)") (class "Default")
      (node (ref "ESP-12") (pin "GPIO10") (pinfunction "10_GPIO10") (pintype "bidirectional"))
    )
    (net (code "60") (name "unconnected-(ESP-12-11-PadCS0)") (class "Default")
      (node (ref "ESP-12") (pin "CS0") (pinfunction "11_CS0") (pintype "bidirectional"))
    )
    (net (code "61") (name "unconnected-(ESP-12-ADC-PadADC0)") (class "Default")
      (node (ref "ESP-12") (pin "ADC0") (pinfunction "ADC_ADC0") (pintype "bidirectional"))
    )
    (net (code "62") (name "unconnected-(U$2-12V-A2-PadA2)") (class "Default")
      (node (ref "U$2") (pin "A2") (pinfunction "12V-A2_A2") (pintype "bidirectional"))
    )
    (net (code "63") (name "unconnected-(U$2-12V-A3-PadA3)") (class "Default")
      (node (ref "U$2") (pin "A3") (pinfunction "12V-A3_A3") (pintype "bidirectional"))
    )
    (net (code "64") (name "unconnected-(U$2-HSIN-A17-PadA17)") (class "Default")
      (node (ref "U$2") (pin "A17") (pinfunction "HSIN-A17_A17") (pintype "bidirectional"))
    )
    (net (code "65") (name "unconnected-(U$2-HSIP-A16-PadA16)") (class "Default")
      (node (ref "U$2") (pin "A16") (pinfunction "HSIP-A16_A16") (pintype "bidirectional"))
    )
    (net (code "66") (name "unconnected-(U$2-HSON-B15-PadB15)") (class "Default")
      (node (ref "U$2") (pin "B15") (pinfunction "HSON-B15_B15") (pintype "bidirectional"))
    )
    (net (code "67") (name "unconnected-(U$2-HSOP-B14-PadB14)") (class "Default")
      (node (ref "U$2") (pin "B14") (pinfunction "HSOP-B14_B14") (pintype "bidirectional"))
    )
    (net (code "68") (name "unconnected-(U$2-JTAG1-B9-PadB9)") (class "Default")
      (node (ref "U$2") (pin "B9") (pinfunction "JTAG1-B9_B9") (pintype "bidirectional"))
    )
    (net (code "69") (name "unconnected-(U$2-JTAG2-A5-PadA5)") (class "Default")
      (node (ref "U$2") (pin "A5") (pinfunction "JTAG2-A5_A5") (pintype "bidirectional"))
    )
    (net (code "70") (name "unconnected-(U$2-JTAG3-A6-PadA6)") (class "Default")
      (node (ref "U$2") (pin "A6") (pinfunction "JTAG3-A6_A6") (pintype "bidirectional"))
    )
    (net (code "71") (name "unconnected-(U$2-JTAG4-A7-PadA7)") (class "Default")
      (node (ref "U$2") (pin "A7") (pinfunction "JTAG4-A7_A7") (pintype "bidirectional"))
    )
    (net (code "72") (name "unconnected-(U$2-JTAG5-A8-PadA8)") (class "Default")
      (node (ref "U$2") (pin "A8") (pinfunction "JTAG5-A8_A8") (pintype "bidirectional"))
    )
    (net (code "73") (name "unconnected-(U$2-PERST#-A11-PadA11)") (class "Default")
      (node (ref "U$2") (pin "A11") (pinfunction "PERST#-A11_A11") (pintype "bidirectional"))
    )
    (net (code "74") (name "unconnected-(U$2-PRSNT1-A1-PadA1)") (class "Default")
      (node (ref "U$2") (pin "A1") (pinfunction "PRSNT1-A1_A1") (pintype "bidirectional"))
    )
    (net (code "75") (name "unconnected-(U$2-PRSNT2-B17-PadB17)") (class "Default")
      (node (ref "U$2") (pin "B17") (pinfunction "PRSNT2-B17_B17") (pintype "bidirectional"))
    )
    (net (code "76") (name "unconnected-(U$2-REFCLK+-A13-PadA13)") (class "Default")
      (node (ref "U$2") (pin "A13") (pinfunction "REFCLK+-A13_A13") (pintype "bidirectional"))
    )
    (net (code "77") (name "unconnected-(U$2-REFCLK--A14-PadA14)") (class "Default")
      (node (ref "U$2") (pin "A14") (pinfunction "REFCLK--A14_A14") (pintype "bidirectional"))
    )
    (net (code "78") (name "unconnected-(U$2-RSVD-B12-PadB12)") (class "Default")
      (node (ref "U$2") (pin "B12") (pinfunction "RSVD-B12_B12") (pintype "bidirectional"))
    )
    (net (code "79") (name "unconnected-(U$2-SMCLK-B5-PadB5)") (class "Default")
      (node (ref "U$2") (pin "B5") (pinfunction "SMCLK-B5_B5") (pintype "bidirectional"))
    )
    (net (code "80") (name "unconnected-(U$2-SMDAT-B6-PadB6)") (class "Default")
      (node (ref "U$2") (pin "B6") (pinfunction "SMDAT-B6_B6") (pintype "bidirectional"))
    )
    (net (code "81") (name "unconnected-(U$2-V12-B1-PadB1)") (class "Default")
      (node (ref "U$2") (pin "B1") (pinfunction "V12-B1_B1") (pintype "bidirectional"))
    )
    (net (code "82") (name "unconnected-(U$2-V12-B2-PadB2)") (class "Default")
      (node (ref "U$2") (pin "B2") (pinfunction "V12-B2_B2") (pintype "bidirectional"))
    )
    (net (code "83") (name "unconnected-(U$2-V12-B3-PadB3)") (class "Default")
      (node (ref "U$2") (pin "B3") (pinfunction "V12-B3_B3") (pintype "bidirectional"))
    )
    (net (code "84") (name "unconnected-(U$2-WAKE#-B11-PadB11)") (class "Default")
      (node (ref "U$2") (pin "B11") (pinfunction "WAKE#-B11_B11") (pintype "bidirectional"))
    )
  )
)
